# 05-USB-UART.net
KiCad netlist of a schematic drawn in Altium Designer
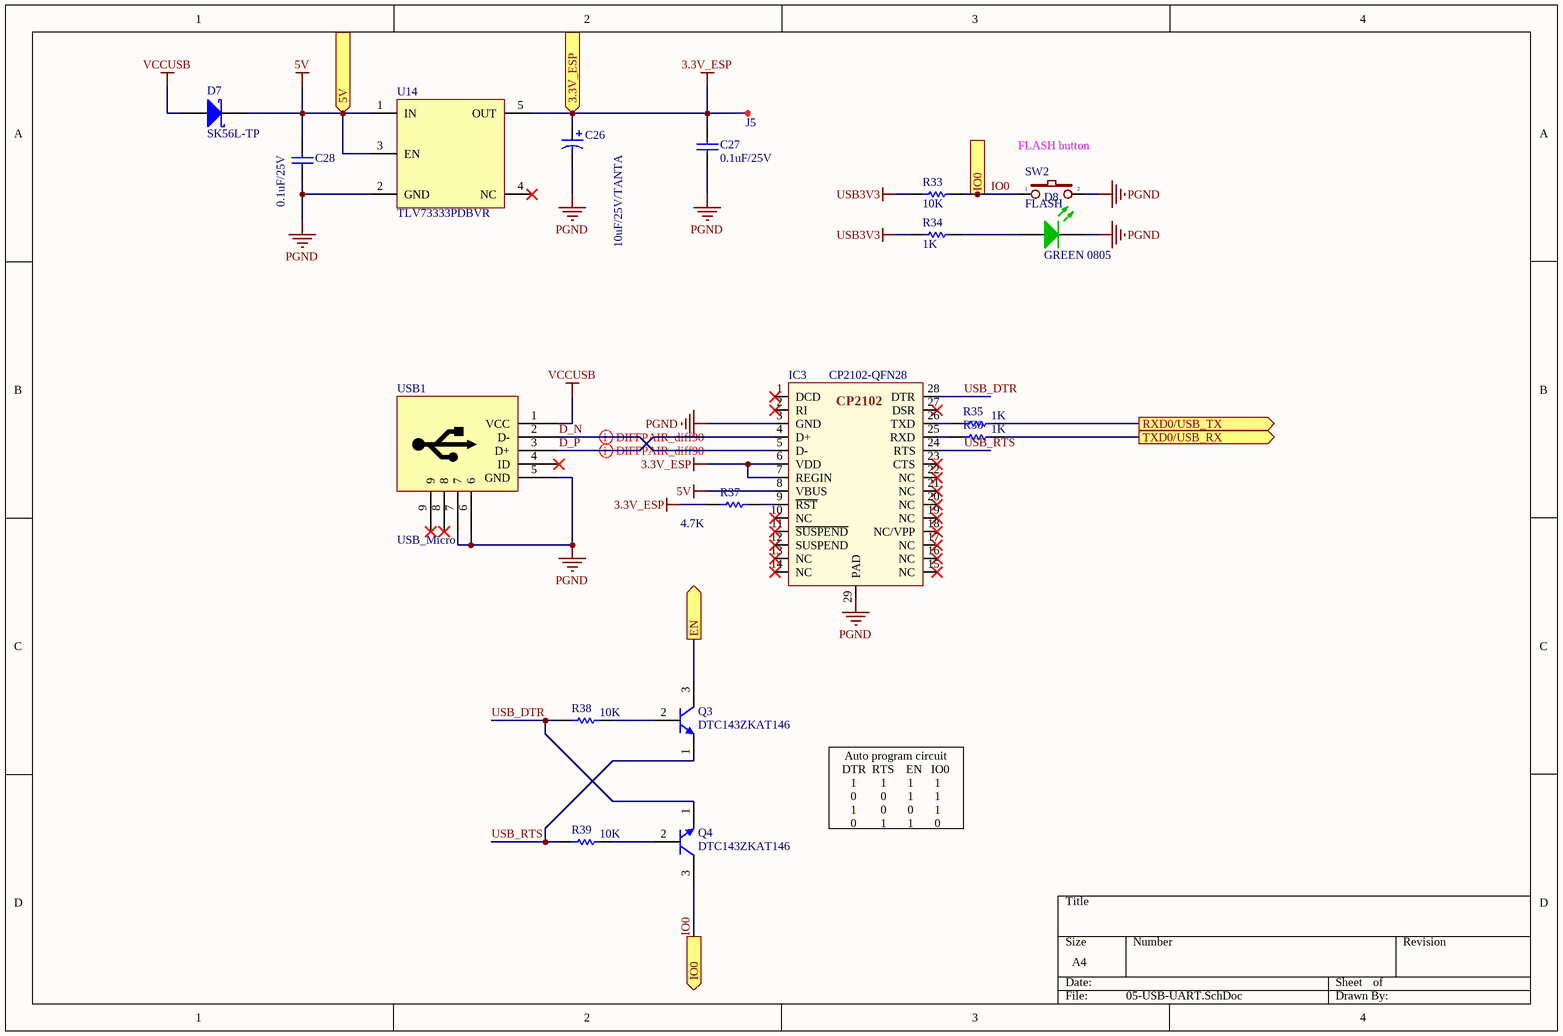
[diagram p0: 05-USB-UART.SchDoc]

(export (version "E")
  (design (tool "Eeschema 10.0.6"))
  (components
    (comp (ref "C26")
      (value "10uF/25V/TANTA")
      (footprint "CAP TANT CASE B SMD")
      (description "10µF Molded Tantalum Capacitors 25V 1411 (3528 Metric) 3 Ohm")
      (fields (field (name "MANUFACTURER") "KEMET"))
      (libsource (lib "GSHT_181013") (part "TAJB106M025RNJ"))
    )
    (comp (ref "C27")
      (value "0.1uF/25V")
      (footprint "CAP_CERA_C2012(CC0805INCH)")
      (description "0.1µF ±10% 25V Ceramic Capacitor X7R 0805 (2012 Metric)")
      (fields (field (name "MANUFACTURER") "KEMET"))
      (libsource (lib "GSHT_181013") (part "0.1uF/50V/C0603/10%"))
    )
    (comp (ref "C28")
      (value "0.1uF/25V")
      (footprint "CAP_CERA_C2012(CC0805INCH)")
      (description "0.1µF ±10% 25V Ceramic Capacitor X7R 0805 (2012 Metric)")
      (libsource (lib "GSHT_181013") (part "0.1uF/50V/C0603/10%"))
    )
    (comp (ref "D7")
      (value "SK56L-TP")
      (footprint "30# SK56L-TPMSCT-ND")
      (description "DIODE SCHOTTKY 60V 5A DO214AB")
      (libsource (lib "GSHT_181013") (part "30# SK56L-TP"))
    )
    (comp (ref "D8")
      (value "GREEN 0805")
      (footprint "Led 0805G")
      (description "Green 571nm LED Indication - Discrete 2V 0805 (2012 Metric)")
      (libsource (lib "GSHT_181013") (part "LED GREEN 0603"))
    )
    (comp (ref "IC3")
      (value "CP2102-QFN28")
      (footprint "CP2102-QFN28")
      (description "USB Bridge, USB to UART USB 2.0 UART Interface 28-QFN (5x5)")
      (libsource (lib "lpson") (part "CP2102"))
    )
    (comp (ref "J5")
      (value "TEST POINT")
      (footprint "TEST POINT 1mm")
      (description "TPoint")
      (libsource (lib "GSHT_181013") (part "PAD 1mm"))
    )
    (comp (ref "Q3")
      (value "DTC143ZKAT146")
      (footprint "6# DTC143ZKAT146-E")
      (description "Pre-Biased Bipolar Transistor (BJT) NPN - Pre-Biased 50V 100mA 250MHz 200mW Surface Mount SMT3")
      (libsource (lib "GSHT_181013") (part "6#DTC143ZKAT146"))
    )
    (comp (ref "Q4")
      (value "DTC143ZKAT146")
      (footprint "6# DTC143ZKAT146-E")
      (description "Pre-Biased Bipolar Transistor (BJT) NPN - Pre-Biased 50V 100mA 250MHz 200mW Surface Mount SMT3")
      (libsource (lib "GSHT_181013") (part "6#DTC143ZKAT146"))
    )
    (comp (ref "R33")
      (value "10K")
      (footprint "Res 0805 SMD")
      (description "10 kOhms ±1% 0.125W, 1/8W Chip Resistor 0805 (2012 Metric) Thick Film")
      (libsource (lib "GSHT_181013") (part "200K/R0603/1%"))
    )
    (comp (ref "R34")
      (value "1K")
      (footprint "Res 0805 SMD")
      (description "1 kOhms ±1% 0.125W, 1/8W Chip Resistor 0805 (2012 Metric) Automotive AEC-Q200 Thick Film")
      (libsource (lib "GSHT_181013") (part "200K/R0603/1%"))
    )
    (comp (ref "R35")
      (value "1K")
      (footprint "Res 0805 SMD")
      (description "1 kOhms ±1% 0.125W, 1/8W Chip Resistor 0805 (2012 Metric) Automotive AEC-Q200 Thick Film")
      (libsource (lib "GSHT_181013") (part "34.8K/R0805/1%"))
    )
    (comp (ref "R36")
      (value "1K")
      (footprint "Res 0805 SMD")
      (description "1 kOhms ±1% 0.125W, 1/8W Chip Resistor 0805 (2012 Metric) Automotive AEC-Q200 Thick Film")
      (libsource (lib "GSHT_181013") (part "34.8K/R0805/1%"))
    )
    (comp (ref "R37")
      (value "4.7K")
      (footprint "Res 0805 SMD")
      (description "4.7 kOhms ±1% 0.125W, 1/8W Chip Resistor 0805 (2012 Metric) Thick Film")
      (libsource (lib "GSHT_181013") (part "34.8K/R0805/1%"))
    )
    (comp (ref "R38")
      (value "10K")
      (footprint "Res 0805 SMD")
      (description "10 kOhms ±1% 0.125W, 1/8W Chip Resistor 0805 (2012 Metric) Thick Film")
      (libsource (lib "GSHT_181013") (part "34.8K/R0805/1%"))
    )
    (comp (ref "R39")
      (value "10K")
      (footprint "Res 0805 SMD")
      (description "10 kOhms ±1% 0.125W, 1/8W Chip Resistor 0805 (2012 Metric) Thick Film")
      (libsource (lib "GSHT_181013") (part "34.8K/R0805/1%"))
    )
    (comp (ref "SW2")
      (value "FLASH")
      (footprint "Button 3x4mm")
      (description "SWITCH TACTILE SPST-NO 0.05A 12V")
      (libsource (lib "lpson") (part "SW2"))
    )
    (comp (ref "U14")
      (value "TLV73333PDBVR")
      (footprint "20# TLV73333PDBVR")
      (description "Linear Voltage Regulator IC Positive Fixed 1 Output 3.3V 300mA SOT-23-5")
      (libsource (lib "GSHT_181013") (part "20#TLV73333PDBVR"))
    )
    (comp (ref "USB1")
      (value "USB_Micro")
      (footprint "USB_MICRO_B - Digikey")
      (description "USB - micro B USB 2.0 Receptacle Connector 5 Position Surface Mount, Right Angle; Through Hole")
      (libsource (lib "lpson") (part "USB_MINI"))
    )
  )
  (nets
    (net (code "1") (name "/D_N") (class "Default")
      (node (ref "IC3") (pin "5") (pinfunction "D-_5") (pintype "passive"))
      (node (ref "USB1") (pin "2") (pinfunction "D-_2") (pintype "passive"))
    )
    (net (code "2") (name "/D_P") (class "Default")
      (node (ref "IC3") (pin "4") (pinfunction "D+_4") (pintype "passive"))
      (node (ref "USB1") (pin "3") (pinfunction "D+_3") (pintype "passive"))
    )
    (net (code "3") (name "/EN") (class "Default")
      (node (ref "Q3") (pin "3") (pinfunction "C_3") (pintype "passive"))
    )
    (net (code "4") (name "/IO0") (class "Default")
      (node (ref "Q4") (pin "3") (pinfunction "C_3") (pintype "passive"))
      (node (ref "R33") (pin "2") (pinfunction "2_2") (pintype "passive"))
      (node (ref "SW2") (pin "1") (pinfunction "1_1") (pintype "passive"))
    )
    (net (code "5") (name "/RXD0{slash}USB_TX") (class "Default")
      (node (ref "R35") (pin "1") (pinfunction "1_1") (pintype "passive"))
    )
    (net (code "6") (name "/TXD0{slash}USB_RX") (class "Default")
      (node (ref "R36") (pin "1") (pinfunction "1_1") (pintype "passive"))
    )
    (net (code "7") (name "/USB_DTR") (class "Default")
      (node (ref "IC3") (pin "28") (pinfunction "DTR_28") (pintype "passive"))
      (node (ref "Q4") (pin "1") (pinfunction "E_1") (pintype "passive"))
      (node (ref "R38") (pin "2") (pinfunction "2_2") (pintype "passive"))
    )
    (net (code "8") (name "/USB_RTS") (class "Default")
      (node (ref "IC3") (pin "24") (pinfunction "RTS_24") (pintype "passive"))
      (node (ref "Q3") (pin "1") (pinfunction "E_1") (pintype "passive"))
      (node (ref "R39") (pin "2") (pinfunction "2_2") (pintype "passive"))
    )
    (net (code "9") (name "3.3V_ESP") (class "Default")
      (node (ref "C26") (pin "1") (pinfunction "1_1") (pintype "passive"))
      (node (ref "C27") (pin "2") (pinfunction "2_2") (pintype "passive"))
      (node (ref "IC3") (pin "6") (pinfunction "VDD_6") (pintype "passive"))
      (node (ref "IC3") (pin "7") (pinfunction "REGIN_7") (pintype "passive"))
      (node (ref "J5") (pin "1") (pinfunction "TP_1") (pintype "passive"))
      (node (ref "R37") (pin "1") (pinfunction "1_1") (pintype "passive"))
      (node (ref "U14") (pin "5") (pinfunction "OUT_5") (pintype "passive"))
    )
    (net (code "10") (name "5V") (class "Default")
      (node (ref "C28") (pin "2") (pinfunction "2_2") (pintype "passive"))
      (node (ref "D7") (pin "2") (pinfunction "K_2") (pintype "passive"))
      (node (ref "IC3") (pin "8") (pinfunction "VBUS_8") (pintype "passive"))
      (node (ref "U14") (pin "1") (pinfunction "IN_1") (pintype "passive"))
      (node (ref "U14") (pin "3") (pinfunction "EN_3") (pintype "passive"))
    )
    (net (code "11") (name "Net-(D8-A)") (class "Default")
      (node (ref "D8") (pin "1") (pinfunction "A_1") (pintype "passive"))
      (node (ref "R34") (pin "2") (pinfunction "2_2") (pintype "passive"))
    )
    (net (code "12") (name "Net-(IC3-RXD)") (class "Default")
      (node (ref "IC3") (pin "25") (pinfunction "RXD_25") (pintype "passive"))
      (node (ref "R36") (pin "2") (pinfunction "2_2") (pintype "passive"))
    )
    (net (code "13") (name "Net-(IC3-TXD)") (class "Default")
      (node (ref "IC3") (pin "26") (pinfunction "TXD_26") (pintype "passive"))
      (node (ref "R35") (pin "2") (pinfunction "2_2") (pintype "passive"))
    )
    (net (code "14") (name "Net-(IC3-~{RST})") (class "Default")
      (node (ref "IC3") (pin "9") (pinfunction "~{RST}_9") (pintype "passive"))
      (node (ref "R37") (pin "2") (pinfunction "2_2") (pintype "passive"))
    )
    (net (code "15") (name "Net-(Q3-B)") (class "Default")
      (node (ref "Q3") (pin "2") (pinfunction "B_2") (pintype "passive"))
      (node (ref "R38") (pin "1") (pinfunction "1_1") (pintype "passive"))
    )
    (net (code "16") (name "Net-(Q4-B)") (class "Default")
      (node (ref "Q4") (pin "2") (pinfunction "B_2") (pintype "passive"))
      (node (ref "R39") (pin "1") (pinfunction "1_1") (pintype "passive"))
    )
    (net (code "17") (name "PGND") (class "Default")
      (node (ref "C26") (pin "2") (pinfunction "2_2") (pintype "passive"))
      (node (ref "C27") (pin "1") (pinfunction "1_1") (pintype "passive"))
      (node (ref "C28") (pin "1") (pinfunction "1_1") (pintype "passive"))
      (node (ref "D8") (pin "2") (pinfunction "K_2") (pintype "passive"))
      (node (ref "IC3") (pin "29") (pinfunction "PAD_29") (pintype "passive"))
      (node (ref "IC3") (pin "3") (pinfunction "GND_3") (pintype "passive"))
      (node (ref "SW2") (pin "2") (pinfunction "2_2") (pintype "passive"))
      (node (ref "U14") (pin "2") (pinfunction "GND_2") (pintype "passive"))
      (node (ref "USB1") (pin "5") (pinfunction "GND_5") (pintype "passive"))
      (node (ref "USB1") (pin "6") (pinfunction "6_6") (pintype "passive"))
      (node (ref "USB1") (pin "7") (pinfunction "7_7") (pintype "passive"))
    )
    (net (code "18") (name "USB3V3") (class "Default")
      (node (ref "R33") (pin "1") (pinfunction "1_1") (pintype "passive"))
      (node (ref "R34") (pin "1") (pinfunction "1_1") (pintype "passive"))
    )
    (net (code "19") (name "VCCUSB") (class "Default")
      (node (ref "D7") (pin "1") (pinfunction "A_1") (pintype "passive"))
      (node (ref "USB1") (pin "1") (pinfunction "VCC_1") (pintype "passive"))
    )
    (net (code "20") (name "unconnected-(IC3-CTS-Pad23)") (class "Default")
      (node (ref "IC3") (pin "23") (pinfunction "CTS_23") (pintype "passive+no_connect"))
    )
    (net (code "21") (name "unconnected-(IC3-DCD-Pad1)") (class "Default")
      (node (ref "IC3") (pin "1") (pinfunction "DCD_1") (pintype "passive+no_connect"))
    )
    (net (code "22") (name "unconnected-(IC3-DSR-Pad27)") (class "Default")
      (node (ref "IC3") (pin "27") (pinfunction "DSR_27") (pintype "passive+no_connect"))
    )
    (net (code "23") (name "unconnected-(IC3-NC-Pad10)") (class "Default")
      (node (ref "IC3") (pin "10") (pinfunction "NC_10") (pintype "passive+no_connect"))
    )
    (net (code "24") (name "unconnected-(IC3-NC-Pad13)") (class "Default")
      (node (ref "IC3") (pin "13") (pinfunction "NC_13") (pintype "passive+no_connect"))
    )
    (net (code "25") (name "unconnected-(IC3-NC-Pad14)") (class "Default")
      (node (ref "IC3") (pin "14") (pinfunction "NC_14") (pintype "passive+no_connect"))
    )
    (net (code "26") (name "unconnected-(IC3-NC-Pad15)") (class "Default")
      (node (ref "IC3") (pin "15") (pinfunction "NC_15") (pintype "passive+no_connect"))
    )
    (net (code "27") (name "unconnected-(IC3-NC-Pad16)") (class "Default")
      (node (ref "IC3") (pin "16") (pinfunction "NC_16") (pintype "passive+no_connect"))
    )
    (net (code "28") (name "unconnected-(IC3-NC-Pad17)") (class "Default")
      (node (ref "IC3") (pin "17") (pinfunction "NC_17") (pintype "passive+no_connect"))
    )
    (net (code "29") (name "unconnected-(IC3-NC-Pad19)") (class "Default")
      (node (ref "IC3") (pin "19") (pinfunction "NC_19") (pintype "passive+no_connect"))
    )
    (net (code "30") (name "unconnected-(IC3-NC-Pad20)") (class "Default")
      (node (ref "IC3") (pin "20") (pinfunction "NC_20") (pintype "passive+no_connect"))
    )
    (net (code "31") (name "unconnected-(IC3-NC-Pad21)") (class "Default")
      (node (ref "IC3") (pin "21") (pinfunction "NC_21") (pintype "passive+no_connect"))
    )
    (net (code "32") (name "unconnected-(IC3-NC-Pad22)") (class "Default")
      (node (ref "IC3") (pin "22") (pinfunction "NC_22") (pintype "passive+no_connect"))
    )
    (net (code "33") (name "unconnected-(IC3-NC{slash}VPP-Pad18)") (class "Default")
      (node (ref "IC3") (pin "18") (pinfunction "NC/VPP_18") (pintype "passive+no_connect"))
    )
    (net (code "34") (name "unconnected-(IC3-RI-Pad2)") (class "Default")
      (node (ref "IC3") (pin "2") (pinfunction "RI_2") (pintype "passive+no_connect"))
    )
    (net (code "35") (name "unconnected-(IC3-SUSPEND-Pad12)") (class "Default")
      (node (ref "IC3") (pin "12") (pinfunction "SUSPEND_12") (pintype "passive+no_connect"))
    )
    (net (code "36") (name "unconnected-(IC3-~{SUSPEND}-Pad11)") (class "Default")
      (node (ref "IC3") (pin "11") (pinfunction "~{SUSPEND}_11") (pintype "passive+no_connect"))
    )
    (net (code "37") (name "unconnected-(U14-NC-Pad4)") (class "Default")
      (node (ref "U14") (pin "4") (pinfunction "NC_4") (pintype "passive+no_connect"))
    )
    (net (code "38") (name "unconnected-(USB1-ID-Pad4)") (class "Default")
      (node (ref "USB1") (pin "4") (pinfunction "ID_4") (pintype "passive+no_connect"))
    )
    (net (code "39") (name "unconnected-(USB1-Pad8)") (class "Default")
      (node (ref "USB1") (pin "8") (pinfunction "8_8") (pintype "passive+no_connect"))
    )
    (net (code "40") (name "unconnected-(USB1-Pad9)") (class "Default")
      (node (ref "USB1") (pin "9") (pinfunction "9_9") (pintype "passive+no_connect"))
    )
  )
)
